# 1_P1.net
KiCad netlist of a schematic drawn in Altium Designer
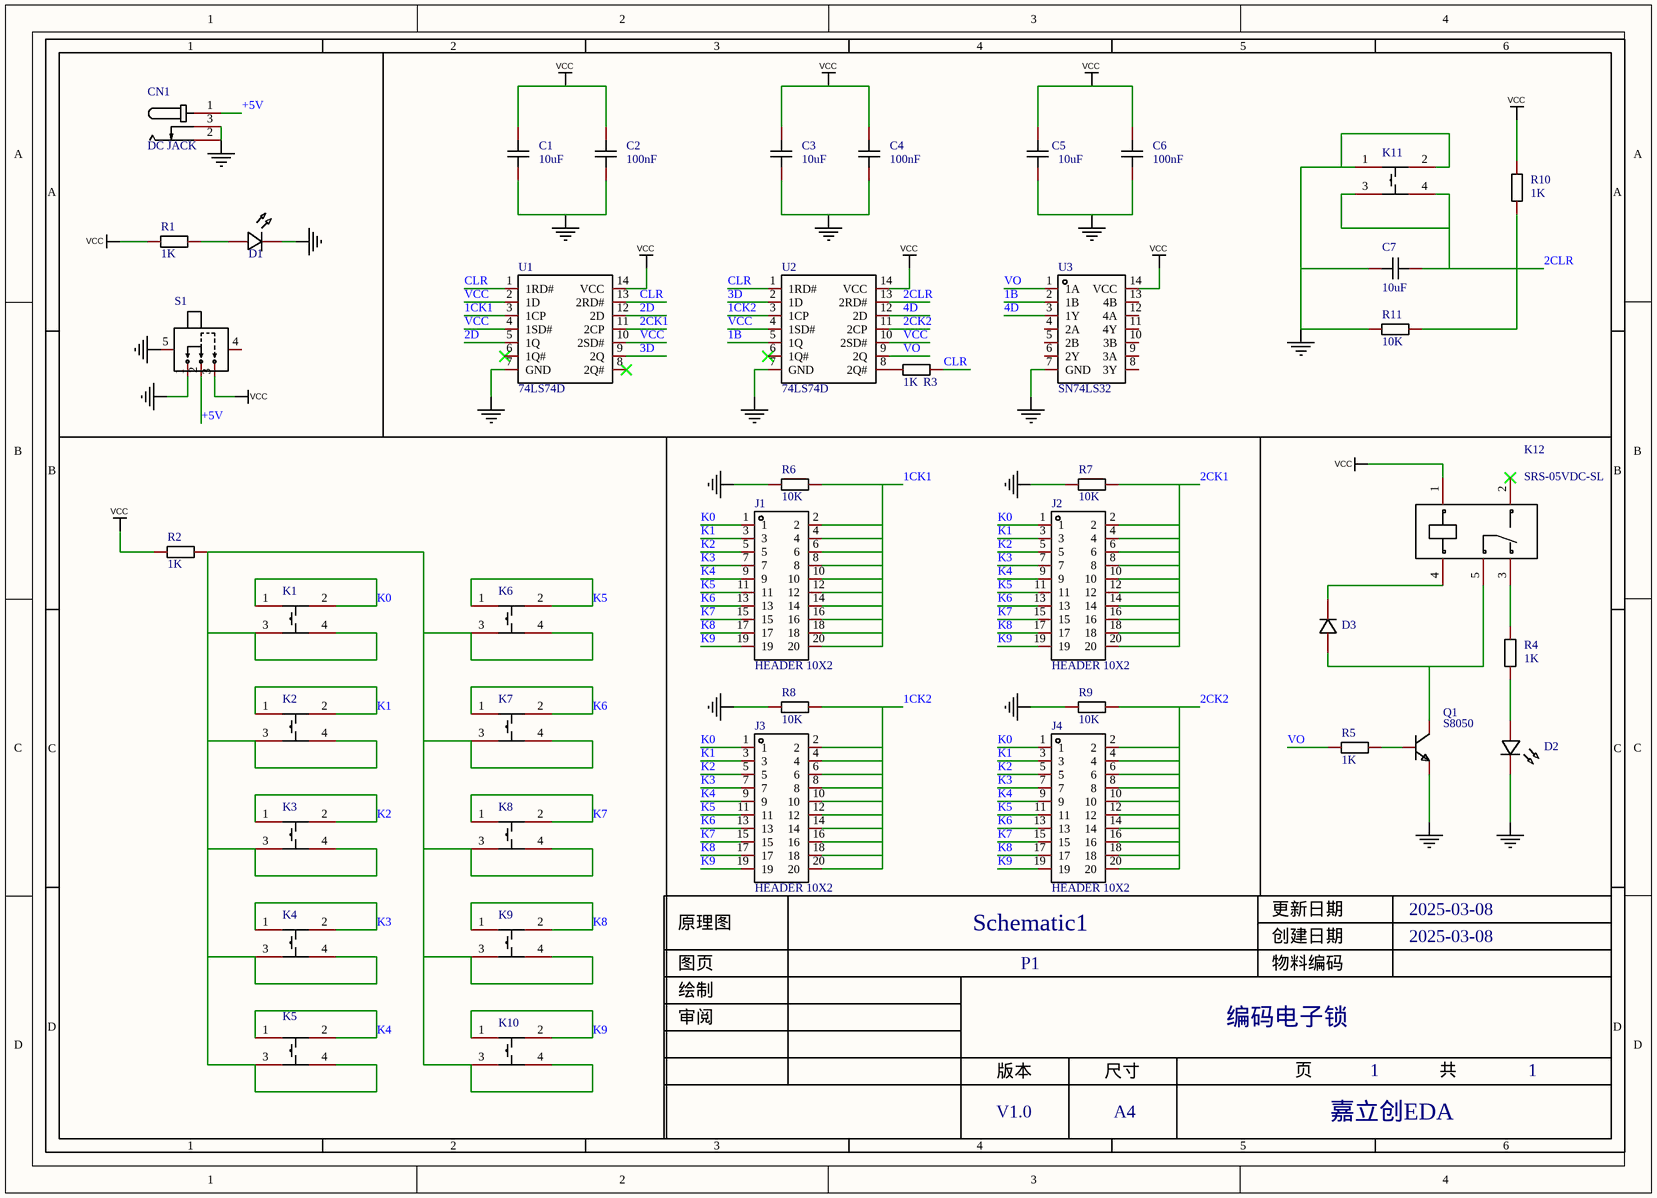
[diagram p0: 1_P1.schdoc]

(export (version "E")
  (design (tool "Eeschema 10.0.6"))
  (components
    (comp (ref "C1")
      (value "10uF")
      (fields (field (name "NAME") "10uF"))
      (libsource (lib "altium-import") (part "root_1_CAP_0805_"))
    )
    (comp (ref "C2")
      (value "100nF")
      (fields (field (name "NAME") "100nF"))
      (libsource (lib "altium-import") (part "root_1_CAP_0805_"))
    )
    (comp (ref "C3")
      (value "10uF")
      (fields (field (name "NAME") "10uF"))
      (libsource (lib "altium-import") (part "root_1_CAP_0805_"))
    )
    (comp (ref "C4")
      (value "100nF")
      (fields (field (name "NAME") "100nF"))
      (libsource (lib "altium-import") (part "root_1_CAP_0805_"))
    )
    (comp (ref "C5")
      (value "10uF")
      (fields (field (name "NAME") "10uF"))
      (libsource (lib "altium-import") (part "root_1_CAP_0805_"))
    )
    (comp (ref "C6")
      (value "100nF")
      (fields (field (name "NAME") "100nF"))
      (libsource (lib "altium-import") (part "root_1_CAP_0805_"))
    )
    (comp (ref "C7")
      (value "10uF")
      (fields (field (name "NAME") "10uF"))
      (libsource (lib "altium-import") (part "root_2_CAP_0805_"))
    )
    (comp (ref "CN1")
      (value "DC JACK")
      (description "连接器类型:DC电源插座;安装方式:弯插;触点内径:2mm;触点外径:6.3mm;额定电流:500mA;额定电压:30V;工作温度范围:-25℃~+70℃;")
      (fields (field (name "NAME") "DC JACK") (field (name "MANUFACTURER") "SHOU HAN(首韩)"))
      (libsource (lib "altium-import") (part "root_0_DC005_"))
    )
    (comp (ref "D1") (value "LED_TH-R_3mm") (libsource (lib "altium-import") (part "root_0_LED_TH-R_3mm_")))
    (comp (ref "D2") (value "LED_TH-R_3mm") (libsource (lib "altium-import") (part "root_3_LED_TH-R_3mm_")))
    (comp (ref "D3")
      (value "LL4148-GS08")
      (description "二极管配置:-;正向压降(Vf):860mV@50mA;直流反向耐压(Vr):75V;平均整流电流(Io):300mA;功率:500mW;反向恢复时间(trr):8ns;")
      (fields (field (name "MANUFACTURER") "VISHAY(威世)"))
      (libsource (lib "altium-import") (part "root_3_LL4148-GS08_"))
    )
    (comp (ref "J1")
      (value "HEADER 10X2")
      (description "插针结构:2x10P;间距:2.54mm;排数:双排;总PIN位数:20P;")
      (fields (field (name "NAME") "HEADER 10X2") (field (name "MANUFACTURER") "ZHOURI(洲日)"))
      (libsource (lib "altium-import") (part "root_0_2.54-2*10_"))
    )
    (comp (ref "J2")
      (value "HEADER 10X2")
      (description "插针结构:2x10P;间距:2.54mm;排数:双排;总PIN位数:20P;")
      (fields (field (name "NAME") "HEADER 10X2") (field (name "MANUFACTURER") "ZHOURI(洲日)"))
      (libsource (lib "altium-import") (part "root_0_2.54-2*10_"))
    )
    (comp (ref "J3")
      (value "HEADER 10X2")
      (description "插针结构:2x10P;间距:2.54mm;排数:双排;总PIN位数:20P;")
      (fields (field (name "NAME") "HEADER 10X2") (field (name "MANUFACTURER") "ZHOURI(洲日)"))
      (libsource (lib "altium-import") (part "root_0_2.54-2*10_"))
    )
    (comp (ref "J4")
      (value "HEADER 10X2")
      (description "插针结构:2x10P;间距:2.54mm;排数:双排;总PIN位数:20P;")
      (fields (field (name "NAME") "HEADER 10X2") (field (name "MANUFACTURER") "ZHOURI(洲日)"))
      (libsource (lib "altium-import") (part "root_0_2.54-2*10_"))
    )
    (comp (ref "K1")
      (value "TS-1002S-04526C")
      (description "电路结构:单刀单掷;按钮形状:圆形按钮;安装方式:立贴;开关长度:6mm;开关宽度:6mm;开关高度:4.5mm;触点电流:50mA;额定电压(DC):12V;带灯:-;机械寿命:-;")
      (fields (field (name "MANUFACTURER") "XUNPU(讯普)"))
      (libsource (lib "altium-import") (part "root_0_TS-1002S-04526C_"))
    )
    (comp (ref "K2")
      (value "TS-1002S-04526C")
      (description "电路结构:单刀单掷;按钮形状:圆形按钮;安装方式:立贴;开关长度:6mm;开关宽度:6mm;开关高度:4.5mm;触点电流:50mA;额定电压(DC):12V;带灯:-;机械寿命:-;")
      (fields (field (name "MANUFACTURER") "XUNPU(讯普)"))
      (libsource (lib "altium-import") (part "root_0_TS-1002S-04526C_"))
    )
    (comp (ref "K3")
      (value "TS-1002S-04526C")
      (description "电路结构:单刀单掷;按钮形状:圆形按钮;安装方式:立贴;开关长度:6mm;开关宽度:6mm;开关高度:4.5mm;触点电流:50mA;额定电压(DC):12V;带灯:-;机械寿命:-;")
      (fields (field (name "MANUFACTURER") "XUNPU(讯普)"))
      (libsource (lib "altium-import") (part "root_0_TS-1002S-04526C_"))
    )
    (comp (ref "K4")
      (value "TS-1002S-04526C")
      (description "电路结构:单刀单掷;按钮形状:圆形按钮;安装方式:立贴;开关长度:6mm;开关宽度:6mm;开关高度:4.5mm;触点电流:50mA;额定电压(DC):12V;带灯:-;机械寿命:-;")
      (fields (field (name "MANUFACTURER") "XUNPU(讯普)"))
      (libsource (lib "altium-import") (part "root_0_TS-1002S-04526C_"))
    )
    (comp (ref "K5")
      (value "TS-1002S-04526C")
      (description "电路结构:单刀单掷;按钮形状:圆形按钮;安装方式:立贴;开关长度:6mm;开关宽度:6mm;开关高度:4.5mm;触点电流:50mA;额定电压(DC):12V;带灯:-;机械寿命:-;")
      (fields (field (name "MANUFACTURER") "XUNPU(讯普)"))
      (libsource (lib "altium-import") (part "root_0_TS-1002S-04526C_"))
    )
    (comp (ref "K6")
      (value "TS-1002S-04526C")
      (description "电路结构:单刀单掷;按钮形状:圆形按钮;安装方式:立贴;开关长度:6mm;开关宽度:6mm;开关高度:4.5mm;触点电流:50mA;额定电压(DC):12V;带灯:-;机械寿命:-;")
      (fields (field (name "MANUFACTURER") "XUNPU(讯普)"))
      (libsource (lib "altium-import") (part "root_0_TS-1002S-04526C_"))
    )
    (comp (ref "K7")
      (value "TS-1002S-04526C")
      (description "电路结构:单刀单掷;按钮形状:圆形按钮;安装方式:立贴;开关长度:6mm;开关宽度:6mm;开关高度:4.5mm;触点电流:50mA;额定电压(DC):12V;带灯:-;机械寿命:-;")
      (fields (field (name "MANUFACTURER") "XUNPU(讯普)"))
      (libsource (lib "altium-import") (part "root_0_TS-1002S-04526C_"))
    )
    (comp (ref "K8")
      (value "TS-1002S-04526C")
      (description "电路结构:单刀单掷;按钮形状:圆形按钮;安装方式:立贴;开关长度:6mm;开关宽度:6mm;开关高度:4.5mm;触点电流:50mA;额定电压(DC):12V;带灯:-;机械寿命:-;")
      (fields (field (name "MANUFACTURER") "XUNPU(讯普)"))
      (libsource (lib "altium-import") (part "root_0_TS-1002S-04526C_"))
    )
    (comp (ref "K9")
      (value "TS-1002S-04526C")
      (description "电路结构:单刀单掷;按钮形状:圆形按钮;安装方式:立贴;开关长度:6mm;开关宽度:6mm;开关高度:4.5mm;触点电流:50mA;额定电压(DC):12V;带灯:-;机械寿命:-;")
      (fields (field (name "MANUFACTURER") "XUNPU(讯普)"))
      (libsource (lib "altium-import") (part "root_0_TS-1002S-04526C_"))
    )
    (comp (ref "K10")
      (value "TS-1002S-04526C")
      (description "电路结构:单刀单掷;按钮形状:圆形按钮;安装方式:立贴;开关长度:6mm;开关宽度:6mm;开关高度:4.5mm;触点电流:50mA;额定电压(DC):12V;带灯:-;机械寿命:-;")
      (fields (field (name "MANUFACTURER") "XUNPU(讯普)"))
      (libsource (lib "altium-import") (part "root_0_TS-1002S-04526C_"))
    )
    (comp (ref "K11")
      (value "TS-1002S-04526C")
      (description "电路结构:单刀单掷;按钮形状:圆形按钮;安装方式:立贴;开关长度:6mm;开关宽度:6mm;开关高度:4.5mm;触点电流:50mA;额定电压(DC):12V;带灯:-;机械寿命:-;")
      (fields (field (name "MANUFACTURER") "XUNPU(讯普)"))
      (libsource (lib "altium-import") (part "root_0_TS-1002S-04526C_"))
    )
    (comp (ref "K12")
      (value "SRS-05VDC-SL")
      (description "线圈电压:5V;触点形式:一组转换:1C(单刀双掷-转换);触点容量(电阻负载):-;最大切换电压:250V@AC;最大切换电流:15A;")
      (fields (field (name "NAME") "SRS-05VDC-SL") (field (name "MANUFACTURER") "松乐"))
      (libsource (lib "altium-import") (part "root_1_mirrored_SRD-05VDC-SL-C_"))
    )
    (comp (ref "Q1")
      (value "S8050")
      (description "晶体管类型:NPN;集电极电流(Ic):500mA;集射极击穿电压(Vceo):25V;耗散功率(Pd):300mW;直流电流增益(hFE):120@500mA,1V;")
      (fields (field (name "NAME") "S8050") (field (name "MANUFACTURER") "MDD(辰达半导体)"))
      (libsource (lib "altium-import") (part "root_0_S8050-J3Y_"))
    )
    (comp (ref "R1")
      (value "1K")
      (fields (field (name "NAME") "1K"))
      (libsource (lib "altium-import") (part "root_0_Res_0805_"))
    )
    (comp (ref "R2")
      (value "1K")
      (fields (field (name "NAME") "1K"))
      (libsource (lib "altium-import") (part "root_0_Res_0805_"))
    )
    (comp (ref "R3")
      (value "1K")
      (fields (field (name "NAME") "1K"))
      (libsource (lib "altium-import") (part "root_0_Res_0805_"))
    )
    (comp (ref "R4")
      (value "1K")
      (fields (field (name "NAME") "1K"))
      (libsource (lib "altium-import") (part "root_1_Res_0805_"))
    )
    (comp (ref "R5")
      (value "1K")
      (fields (field (name "NAME") "1K"))
      (libsource (lib "altium-import") (part "root_0_Res_0805_"))
    )
    (comp (ref "R6")
      (value "10K")
      (fields (field (name "NAME") "10K"))
      (libsource (lib "altium-import") (part "root_0_Res_0805_"))
    )
    (comp (ref "R7")
      (value "10K")
      (fields (field (name "NAME") "10K"))
      (libsource (lib "altium-import") (part "root_0_Res_0805_"))
    )
    (comp (ref "R8")
      (value "10K")
      (fields (field (name "NAME") "10K"))
      (libsource (lib "altium-import") (part "root_0_Res_0805_"))
    )
    (comp (ref "R9")
      (value "10K")
      (fields (field (name "NAME") "10K"))
      (libsource (lib "altium-import") (part "root_0_Res_0805_"))
    )
    (comp (ref "R10")
      (value "1K")
      (fields (field (name "NAME") "1K"))
      (libsource (lib "altium-import") (part "root_1_Res_0805_"))
    )
    (comp (ref "R11")
      (value "10K")
      (fields (field (name "NAME") "10K"))
      (libsource (lib "altium-import") (part "root_2_Res_0805_"))
    )
    (comp (ref "S1")
      (value "SS12F44G5")
      (description "拨动开关 立式直脚插件 二档 柄高5mm")
      (fields (field (name "MANUFACTURER") "HanElectricity(瀚源)"))
      (libsource (lib "altium-import") (part "root_0_SS12F44G5_"))
    )
    (comp (ref "U1")
      (value "74LS74D")
      (description "类型:D-型;工作电压:2V~6V;时钟频率(fc):82MHz;元件数:2;每个元件位数:1;静态电流(Iq):40uA;")
      (fields (field (name "NAME") "74LS74D") (field (name "MANUFACTURER") "LX(灵星芯微)"))
      (libsource (lib "altium-import") (part "root_0_SN74LS74N_"))
    )
    (comp (ref "U2")
      (value "74LS74D")
      (description "类型:D-型;工作电压:2V~6V;时钟频率(fc):82MHz;元件数:2;每个元件位数:1;静态电流(Iq):40uA;")
      (fields (field (name "NAME") "74LS74D") (field (name "MANUFACTURER") "LX(灵星芯微)"))
      (libsource (lib "altium-import") (part "root_0_SN74LS74N_"))
    )
    (comp (ref "U3")
      (value "SN74LS32")
      (description "逻辑类型:或门;通道数:4;电源电压:4.75V~5.25V;最大传播延迟:22ns@5V,15pF;")
      (fields (field (name "NAME") "SN74LS32") (field (name "MANUFACTURER") "TI(德州仪器)"))
      (libsource (lib "altium-import") (part "root_0_SN74LS32N_"))
    )
  )
  (nets
    (net (code "1") (name "/+5V") (class "Default")
      (node (ref "CN1") (pin "1") (pinfunction "1_1") (pintype "passive"))
      (node (ref "S1") (pin "2") (pinfunction "2_2") (pintype "passive"))
    )
    (net (code "2") (name "/1B") (class "Default")
      (node (ref "U2") (pin "5") (pinfunction "1Q_5") (pintype "passive"))
      (node (ref "U3") (pin "2") (pinfunction "1B_2") (pintype "passive"))
    )
    (net (code "3") (name "/1CK1") (class "Default")
      (node (ref "J1") (pin "10") (pinfunction "10_10") (pintype "passive"))
      (node (ref "J1") (pin "12") (pinfunction "12_12") (pintype "passive"))
      (node (ref "J1") (pin "14") (pinfunction "14_14") (pintype "passive"))
      (node (ref "J1") (pin "16") (pinfunction "16_16") (pintype "passive"))
      (node (ref "J1") (pin "18") (pinfunction "18_18") (pintype "passive"))
      (node (ref "J1") (pin "2") (pinfunction "2_2") (pintype "passive"))
      (node (ref "J1") (pin "20") (pinfunction "20_20") (pintype "passive"))
      (node (ref "J1") (pin "4") (pinfunction "4_4") (pintype "passive"))
      (node (ref "J1") (pin "6") (pinfunction "6_6") (pintype "passive"))
      (node (ref "J1") (pin "8") (pinfunction "8_8") (pintype "passive"))
      (node (ref "R6") (pin "2") (pinfunction "2_2") (pintype "passive"))
      (node (ref "U1") (pin "3") (pinfunction "1CP_3") (pintype "passive"))
    )
    (net (code "4") (name "/1CK2") (class "Default")
      (node (ref "J3") (pin "10") (pinfunction "10_10") (pintype "passive"))
      (node (ref "J3") (pin "12") (pinfunction "12_12") (pintype "passive"))
      (node (ref "J3") (pin "14") (pinfunction "14_14") (pintype "passive"))
      (node (ref "J3") (pin "16") (pinfunction "16_16") (pintype "passive"))
      (node (ref "J3") (pin "18") (pinfunction "18_18") (pintype "passive"))
      (node (ref "J3") (pin "2") (pinfunction "2_2") (pintype "passive"))
      (node (ref "J3") (pin "20") (pinfunction "20_20") (pintype "passive"))
      (node (ref "J3") (pin "4") (pinfunction "4_4") (pintype "passive"))
      (node (ref "J3") (pin "6") (pinfunction "6_6") (pintype "passive"))
      (node (ref "J3") (pin "8") (pinfunction "8_8") (pintype "passive"))
      (node (ref "R8") (pin "2") (pinfunction "2_2") (pintype "passive"))
      (node (ref "U2") (pin "3") (pinfunction "1CP_3") (pintype "passive"))
    )
    (net (code "5") (name "/2CK1") (class "Default")
      (node (ref "J2") (pin "10") (pinfunction "10_10") (pintype "passive"))
      (node (ref "J2") (pin "12") (pinfunction "12_12") (pintype "passive"))
      (node (ref "J2") (pin "14") (pinfunction "14_14") (pintype "passive"))
      (node (ref "J2") (pin "16") (pinfunction "16_16") (pintype "passive"))
      (node (ref "J2") (pin "18") (pinfunction "18_18") (pintype "passive"))
      (node (ref "J2") (pin "2") (pinfunction "2_2") (pintype "passive"))
      (node (ref "J2") (pin "20") (pinfunction "20_20") (pintype "passive"))
      (node (ref "J2") (pin "4") (pinfunction "4_4") (pintype "passive"))
      (node (ref "J2") (pin "6") (pinfunction "6_6") (pintype "passive"))
      (node (ref "J2") (pin "8") (pinfunction "8_8") (pintype "passive"))
      (node (ref "R7") (pin "2") (pinfunction "2_2") (pintype "passive"))
      (node (ref "U1") (pin "11") (pinfunction "2CP_11") (pintype "passive"))
    )
    (net (code "6") (name "/2CK2") (class "Default")
      (node (ref "J4") (pin "10") (pinfunction "10_10") (pintype "passive"))
      (node (ref "J4") (pin "12") (pinfunction "12_12") (pintype "passive"))
      (node (ref "J4") (pin "14") (pinfunction "14_14") (pintype "passive"))
      (node (ref "J4") (pin "16") (pinfunction "16_16") (pintype "passive"))
      (node (ref "J4") (pin "18") (pinfunction "18_18") (pintype "passive"))
      (node (ref "J4") (pin "2") (pinfunction "2_2") (pintype "passive"))
      (node (ref "J4") (pin "20") (pinfunction "20_20") (pintype "passive"))
      (node (ref "J4") (pin "4") (pinfunction "4_4") (pintype "passive"))
      (node (ref "J4") (pin "6") (pinfunction "6_6") (pintype "passive"))
      (node (ref "J4") (pin "8") (pinfunction "8_8") (pintype "passive"))
      (node (ref "R9") (pin "2") (pinfunction "2_2") (pintype "passive"))
      (node (ref "U2") (pin "11") (pinfunction "2CP_11") (pintype "passive"))
    )
    (net (code "7") (name "/2CLR") (class "Default")
      (node (ref "C7") (pin "1") (pinfunction "1_1") (pintype "passive"))
      (node (ref "K11") (pin "3") (pinfunction "3_3") (pintype "passive"))
      (node (ref "K11") (pin "4") (pinfunction "4_4") (pintype "passive"))
      (node (ref "R10") (pin "1") (pinfunction "1_1") (pintype "passive"))
      (node (ref "R11") (pin "1") (pinfunction "1_1") (pintype "passive"))
      (node (ref "U2") (pin "13") (pinfunction "2RD#_13") (pintype "passive"))
    )
    (net (code "8") (name "/2D") (class "Default")
      (node (ref "U1") (pin "12") (pinfunction "2D_12") (pintype "passive"))
      (node (ref "U1") (pin "5") (pinfunction "1Q_5") (pintype "passive"))
    )
    (net (code "9") (name "/3D") (class "Default")
      (node (ref "U1") (pin "9") (pinfunction "2Q_9") (pintype "passive"))
      (node (ref "U2") (pin "2") (pinfunction "1D_2") (pintype "passive"))
    )
    (net (code "10") (name "/4D") (class "Default")
      (node (ref "U2") (pin "12") (pinfunction "2D_12") (pintype "passive"))
      (node (ref "U3") (pin "3") (pinfunction "1Y_3") (pintype "passive"))
    )
    (net (code "11") (name "/CLR") (class "Default")
      (node (ref "R3") (pin "2") (pinfunction "2_2") (pintype "passive"))
      (node (ref "U1") (pin "1") (pinfunction "1RD#_1") (pintype "passive"))
      (node (ref "U1") (pin "13") (pinfunction "2RD#_13") (pintype "passive"))
      (node (ref "U2") (pin "1") (pinfunction "1RD#_1") (pintype "passive"))
    )
    (net (code "12") (name "/K0") (class "Default")
      (node (ref "J1") (pin "1") (pinfunction "1_1") (pintype "passive"))
      (node (ref "J2") (pin "1") (pinfunction "1_1") (pintype "passive"))
      (node (ref "J3") (pin "1") (pinfunction "1_1") (pintype "passive"))
      (node (ref "J4") (pin "1") (pinfunction "1_1") (pintype "passive"))
      (node (ref "K1") (pin "1") (pinfunction "1_1") (pintype "passive"))
      (node (ref "K1") (pin "2") (pinfunction "2_2") (pintype "passive"))
    )
    (net (code "13") (name "/K1") (class "Default")
      (node (ref "J1") (pin "3") (pinfunction "3_3") (pintype "passive"))
      (node (ref "J2") (pin "3") (pinfunction "3_3") (pintype "passive"))
      (node (ref "J3") (pin "3") (pinfunction "3_3") (pintype "passive"))
      (node (ref "J4") (pin "3") (pinfunction "3_3") (pintype "passive"))
      (node (ref "K2") (pin "1") (pinfunction "1_1") (pintype "passive"))
      (node (ref "K2") (pin "2") (pinfunction "2_2") (pintype "passive"))
    )
    (net (code "14") (name "/K2") (class "Default")
      (node (ref "J1") (pin "5") (pinfunction "5_5") (pintype "passive"))
      (node (ref "J2") (pin "5") (pinfunction "5_5") (pintype "passive"))
      (node (ref "J3") (pin "5") (pinfunction "5_5") (pintype "passive"))
      (node (ref "J4") (pin "5") (pinfunction "5_5") (pintype "passive"))
      (node (ref "K3") (pin "1") (pinfunction "1_1") (pintype "passive"))
      (node (ref "K3") (pin "2") (pinfunction "2_2") (pintype "passive"))
    )
    (net (code "15") (name "/K3") (class "Default")
      (node (ref "J1") (pin "7") (pinfunction "7_7") (pintype "passive"))
      (node (ref "J2") (pin "7") (pinfunction "7_7") (pintype "passive"))
      (node (ref "J3") (pin "7") (pinfunction "7_7") (pintype "passive"))
      (node (ref "J4") (pin "7") (pinfunction "7_7") (pintype "passive"))
      (node (ref "K4") (pin "1") (pinfunction "1_1") (pintype "passive"))
      (node (ref "K4") (pin "2") (pinfunction "2_2") (pintype "passive"))
    )
    (net (code "16") (name "/K4") (class "Default")
      (node (ref "J1") (pin "9") (pinfunction "9_9") (pintype "passive"))
      (node (ref "J2") (pin "9") (pinfunction "9_9") (pintype "passive"))
      (node (ref "J3") (pin "9") (pinfunction "9_9") (pintype "passive"))
      (node (ref "J4") (pin "9") (pinfunction "9_9") (pintype "passive"))
      (node (ref "K5") (pin "1") (pinfunction "1_1") (pintype "passive"))
      (node (ref "K5") (pin "2") (pinfunction "2_2") (pintype "passive"))
    )
    (net (code "17") (name "/K5") (class "Default")
      (node (ref "J1") (pin "11") (pinfunction "11_11") (pintype "passive"))
      (node (ref "J2") (pin "11") (pinfunction "11_11") (pintype "passive"))
      (node (ref "J3") (pin "11") (pinfunction "11_11") (pintype "passive"))
      (node (ref "J4") (pin "11") (pinfunction "11_11") (pintype "passive"))
      (node (ref "K6") (pin "1") (pinfunction "1_1") (pintype "passive"))
      (node (ref "K6") (pin "2") (pinfunction "2_2") (pintype "passive"))
    )
    (net (code "18") (name "/K6") (class "Default")
      (node (ref "J1") (pin "13") (pinfunction "13_13") (pintype "passive"))
      (node (ref "J2") (pin "13") (pinfunction "13_13") (pintype "passive"))
      (node (ref "J3") (pin "13") (pinfunction "13_13") (pintype "passive"))
      (node (ref "J4") (pin "13") (pinfunction "13_13") (pintype "passive"))
      (node (ref "K7") (pin "1") (pinfunction "1_1") (pintype "passive"))
      (node (ref "K7") (pin "2") (pinfunction "2_2") (pintype "passive"))
    )
    (net (code "19") (name "/K7") (class "Default")
      (node (ref "J1") (pin "15") (pinfunction "15_15") (pintype "passive"))
      (node (ref "J2") (pin "15") (pinfunction "15_15") (pintype "passive"))
      (node (ref "J3") (pin "15") (pinfunction "15_15") (pintype "passive"))
      (node (ref "J4") (pin "15") (pinfunction "15_15") (pintype "passive"))
      (node (ref "K8") (pin "1") (pinfunction "1_1") (pintype "passive"))
      (node (ref "K8") (pin "2") (pinfunction "2_2") (pintype "passive"))
    )
    (net (code "20") (name "/K8") (class "Default")
      (node (ref "J1") (pin "17") (pinfunction "17_17") (pintype "passive"))
      (node (ref "J2") (pin "17") (pinfunction "17_17") (pintype "passive"))
      (node (ref "J3") (pin "17") (pinfunction "17_17") (pintype "passive"))
      (node (ref "J4") (pin "17") (pinfunction "17_17") (pintype "passive"))
      (node (ref "K9") (pin "1") (pinfunction "1_1") (pintype "passive"))
      (node (ref "K9") (pin "2") (pinfunction "2_2") (pintype "passive"))
    )
    (net (code "21") (name "/K9") (class "Default")
      (node (ref "J1") (pin "19") (pinfunction "19_19") (pintype "passive"))
      (node (ref "J2") (pin "19") (pinfunction "19_19") (pintype "passive"))
      (node (ref "J3") (pin "19") (pinfunction "19_19") (pintype "passive"))
      (node (ref "J4") (pin "19") (pinfunction "19_19") (pintype "passive"))
      (node (ref "K10") (pin "1") (pinfunction "1_1") (pintype "passive"))
      (node (ref "K10") (pin "2") (pinfunction "2_2") (pintype "passive"))
    )
    (net (code "22") (name "/VO") (class "Default")
      (node (ref "R5") (pin "1") (pinfunction "1_1") (pintype "passive"))
      (node (ref "U2") (pin "9") (pinfunction "2Q_9") (pintype "passive"))
      (node (ref "U3") (pin "1") (pinfunction "1A_1") (pintype "passive"))
    )
    (net (code "23") (name "<NO NET>") (class "Default")
      (node (ref "C1") (pin "1") (pinfunction "1_1") (pintype "passive"))
      (node (ref "C2") (pin "1") (pinfunction "1_1") (pintype "passive"))
      (node (ref "C3") (pin "1") (pinfunction "1_1") (pintype "passive"))
      (node (ref "C4") (pin "1") (pinfunction "1_1") (pintype "passive"))
      (node (ref "C5") (pin "1") (pinfunction "1_1") (pintype "passive"))
      (node (ref "C6") (pin "1") (pinfunction "1_1") (pintype "passive"))
      (node (ref "C7") (pin "2") (pinfunction "2_2") (pintype "passive"))
      (node (ref "CN1") (pin "2") (pinfunction "2_2") (pintype "passive"))
      (node (ref "CN1") (pin "3") (pinfunction "3_3") (pintype "passive"))
      (node (ref "D1") (pin "2") (pinfunction "A_2") (pintype "passive"))
      (node (ref "D2") (pin "2") (pinfunction "A_2") (pintype "passive"))
      (node (ref "K11") (pin "1") (pinfunction "1_1") (pintype "passive"))
      (node (ref "K11") (pin "2") (pinfunction "2_2") (pintype "passive"))
      (node (ref "Q1") (pin "2") (pinfunction "E_2") (pintype "passive"))
      (node (ref "R11") (pin "2") (pinfunction "2_2") (pintype "passive"))
      (node (ref "R6") (pin "1") (pinfunction "1_1") (pintype "passive"))
      (node (ref "R7") (pin "1") (pinfunction "1_1") (pintype "passive"))
      (node (ref "R8") (pin "1") (pinfunction "1_1") (pintype "passive"))
      (node (ref "R9") (pin "1") (pinfunction "1_1") (pintype "passive"))
      (node (ref "S1") (pin "1") (pinfunction "1_1") (pintype "passive"))
      (node (ref "S1") (pin "5") (pinfunction "5_5") (pintype "passive"))
      (node (ref "U1") (pin "7") (pinfunction "GND_7") (pintype "passive"))
      (node (ref "U2") (pin "7") (pinfunction "GND_7") (pintype "passive"))
      (node (ref "U3") (pin "7") (pinfunction "GND_7") (pintype "passive"))
    )
    (net (code "24") (name "Net-(D1-C)") (class "Default")
      (node (ref "D1") (pin "1") (pinfunction "C_1") (pintype "passive"))
      (node (ref "R1") (pin "2") (pinfunction "2_2") (pintype "passive"))
    )
    (net (code "25") (name "Net-(D2-C)") (class "Default")
      (node (ref "D2") (pin "1") (pinfunction "C_1") (pintype "passive"))
      (node (ref "R4") (pin "1") (pinfunction "1_1") (pintype "passive"))
    )
    (net (code "26") (name "Net-(D3-A)") (class "Default")
      (node (ref "D3") (pin "2") (pinfunction "A_2") (pintype "passive"))
      (node (ref "K12") (pin "5") (pinfunction "5_5") (pintype "passive"))
      (node (ref "Q1") (pin "3") (pinfunction "C_3") (pintype "passive"))
    )
    (net (code "27") (name "Net-(D3-C)") (class "Default")
      (node (ref "D3") (pin "1") (pinfunction "C_1") (pintype "passive"))
      (node (ref "K12") (pin "4") (pinfunction "4_4") (pintype "passive"))
    )
    (net (code "28") (name "Net-(K1-Pad3)") (class "Default")
      (node (ref "K1") (pin "3") (pinfunction "3_3") (pintype "passive"))
      (node (ref "K1") (pin "4") (pinfunction "4_4") (pintype "passive"))
      (node (ref "K10") (pin "3") (pinfunction "3_3") (pintype "passive"))
      (node (ref "K10") (pin "4") (pinfunction "4_4") (pintype "passive"))
      (node (ref "K2") (pin "3") (pinfunction "3_3") (pintype "passive"))
      (node (ref "K2") (pin "4") (pinfunction "4_4") (pintype "passive"))
      (node (ref "K3") (pin "3") (pinfunction "3_3") (pintype "passive"))
      (node (ref "K3") (pin "4") (pinfunction "4_4") (pintype "passive"))
      (node (ref "K4") (pin "3") (pinfunction "3_3") (pintype "passive"))
      (node (ref "K4") (pin "4") (pinfunction "4_4") (pintype "passive"))
      (node (ref "K5") (pin "3") (pinfunction "3_3") (pintype "passive"))
      (node (ref "K5") (pin "4") (pinfunction "4_4") (pintype "passive"))
      (node (ref "K6") (pin "3") (pinfunction "3_3") (pintype "passive"))
      (node (ref "K6") (pin "4") (pinfunction "4_4") (pintype "passive"))
      (node (ref "K7") (pin "3") (pinfunction "3_3") (pintype "passive"))
      (node (ref "K7") (pin "4") (pinfunction "4_4") (pintype "passive"))
      (node (ref "K8") (pin "3") (pinfunction "3_3") (pintype "passive"))
      (node (ref "K8") (pin "4") (pinfunction "4_4") (pintype "passive"))
      (node (ref "K9") (pin "3") (pinfunction "3_3") (pintype "passive"))
      (node (ref "K9") (pin "4") (pinfunction "4_4") (pintype "passive"))
      (node (ref "R2") (pin "2") (pinfunction "2_2") (pintype "passive"))
    )
    (net (code "29") (name "Net-(K12-Pad3)") (class "Default")
      (node (ref "K12") (pin "3") (pinfunction "3_3") (pintype "passive"))
      (node (ref "R4") (pin "2") (pinfunction "2_2") (pintype "passive"))
    )
    (net (code "30") (name "Net-(Q1-B)") (class "Default")
      (node (ref "Q1") (pin "1") (pinfunction "B_1") (pintype "passive"))
      (node (ref "R5") (pin "2") (pinfunction "2_2") (pintype "passive"))
    )
    (net (code "31") (name "Net-(U2-2Q#)") (class "Default")
      (node (ref "R3") (pin "1") (pinfunction "1_1") (pintype "passive"))
      (node (ref "U2") (pin "8") (pinfunction "2Q#_8") (pintype "passive"))
    )
    (net (code "32") (name "VCC") (class "Default")
      (node (ref "C1") (pin "2") (pinfunction "2_2") (pintype "passive"))
      (node (ref "C2") (pin "2") (pinfunction "2_2") (pintype "passive"))
      (node (ref "C3") (pin "2") (pinfunction "2_2") (pintype "passive"))
      (node (ref "C4") (pin "2") (pinfunction "2_2") (pintype "passive"))
      (node (ref "C5") (pin "2") (pinfunction "2_2") (pintype "passive"))
      (node (ref "C6") (pin "2") (pinfunction "2_2") (pintype "passive"))
      (node (ref "K12") (pin "1") (pinfunction "1_1") (pintype "passive"))
      (node (ref "R1") (pin "1") (pinfunction "1_1") (pintype "passive"))
      (node (ref "R10") (pin "2") (pinfunction "2_2") (pintype "passive"))
      (node (ref "R2") (pin "1") (pinfunction "1_1") (pintype "passive"))
      (node (ref "S1") (pin "3") (pinfunction "3_3") (pintype "passive"))
      (node (ref "U1") (pin "10") (pinfunction "2SD#_10") (pintype "passive"))
      (node (ref "U1") (pin "14") (pinfunction "VCC_14") (pintype "passive"))
      (node (ref "U1") (pin "2") (pinfunction "1D_2") (pintype "passive"))
      (node (ref "U1") (pin "4") (pinfunction "1SD#_4") (pintype "passive"))
      (node (ref "U2") (pin "10") (pinfunction "2SD#_10") (pintype "passive"))
      (node (ref "U2") (pin "14") (pinfunction "VCC_14") (pintype "passive"))
      (node (ref "U2") (pin "4") (pinfunction "1SD#_4") (pintype "passive"))
      (node (ref "U3") (pin "14") (pinfunction "VCC_14") (pintype "passive"))
    )
    (net (code "33") (name "unconnected-(K12-Pad2)") (class "Default")
      (node (ref "K12") (pin "2") (pinfunction "2_2") (pintype "passive+no_connect"))
    )
    (net (code "34") (name "unconnected-(S1-Pad4)") (class "Default")
      (node (ref "S1") (pin "4") (pinfunction "4_4") (pintype "passive"))
    )
    (net (code "35") (name "unconnected-(U1-1Q#-Pad6)") (class "Default")
      (node (ref "U1") (pin "6") (pinfunction "1Q#_6") (pintype "passive+no_connect"))
    )
    (net (code "36") (name "unconnected-(U1-2Q#-Pad8)") (class "Default")
      (node (ref "U1") (pin "8") (pinfunction "2Q#_8") (pintype "passive+no_connect"))
    )
    (net (code "37") (name "unconnected-(U2-1Q#-Pad6)") (class "Default")
      (node (ref "U2") (pin "6") (pinfunction "1Q#_6") (pintype "passive+no_connect"))
    )
    (net (code "38") (name "unconnected-(U3-2A-Pad4)") (class "Default")
      (node (ref "U3") (pin "4") (pinfunction "2A_4") (pintype "passive"))
    )
    (net (code "39") (name "unconnected-(U3-2B-Pad5)") (class "Default")
      (node (ref "U3") (pin "5") (pinfunction "2B_5") (pintype "passive"))
    )
    (net (code "40") (name "unconnected-(U3-2Y-Pad6)") (class "Default")
      (node (ref "U3") (pin "6") (pinfunction "2Y_6") (pintype "passive"))
    )
    (net (code "41") (name "unconnected-(U3-3A-Pad9)") (class "Default")
      (node (ref "U3") (pin "9") (pinfunction "3A_9") (pintype "passive"))
    )
    (net (code "42") (name "unconnected-(U3-3B-Pad10)") (class "Default")
      (node (ref "U3") (pin "10") (pinfunction "3B_10") (pintype "passive"))
    )
    (net (code "43") (name "unconnected-(U3-3Y-Pad8)") (class "Default")
      (node (ref "U3") (pin "8") (pinfunction "3Y_8") (pintype "passive"))
    )
    (net (code "44") (name "unconnected-(U3-4A-Pad12)") (class "Default")
      (node (ref "U3") (pin "12") (pinfunction "4A_12") (pintype "passive"))
    )
    (net (code "45") (name "unconnected-(U3-4B-Pad13)") (class "Default")
      (node (ref "U3") (pin "13") (pinfunction "4B_13") (pintype "passive"))
    )
    (net (code "46") (name "unconnected-(U3-4Y-Pad11)") (class "Default")
      (node (ref "U3") (pin "11") (pinfunction "4Y_11") (pintype "passive"))
    )
  )
)
